# input.net
KiCad netlist of a schematic drawn in Altium Designer
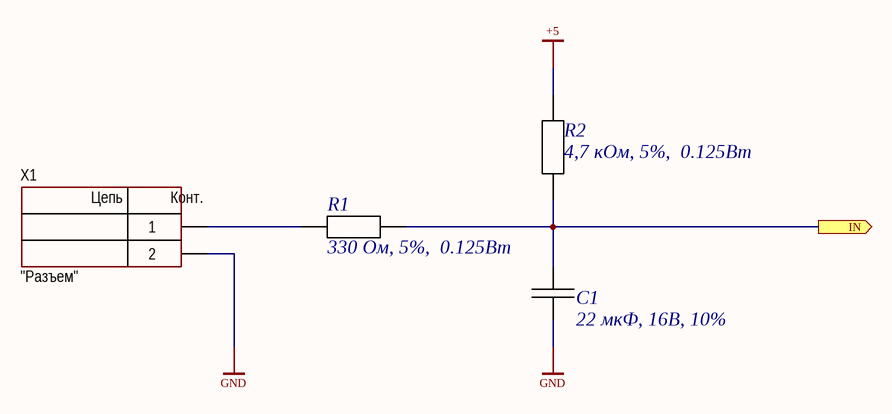
[diagram p0: input.SchDoc]

(export (version "E")
  (design (tool "Eeschema 10.0.6"))
  (components
    (comp (ref "C1")
      (value "22 мкФ, 16В, 10%")
      (footprint "CAP: 1206")
      (description "Конденсатор")
      (fields
        (field (name "PARTNUMBER") "GRM31CR61C226KE15L")
        (field (name "MANUFACTURER") "Murata Manufacturing")
      )
      (libsource (lib "AltiumDatabaseVM") (part "CAP_1"))
    )
    (comp (ref "R1")
      (value "330 Ом, 5%,  0.125Вт")
      (footprint "RES: 0805")
      (description "Бескорпусные толстопленочные резисторы")
      (fields (field (name "POWER") "0,25") (field (name "PARTNUMBER") "RC0805JR-07330RL"))
      (libsource (lib "") (part "Resistor_1"))
    )
    (comp (ref "R2")
      (value "4,7 кОм, 5%,  0.125Вт")
      (footprint "RES: 0805")
      (description "Бескорпусные толстопленочные резисторы")
      (fields (field (name "POWER") "0,25") (field (name "PARTNUMBER") "RC0805JR-074K7L"))
      (libsource (lib "AltiumDatabaseVM") (part "Resistor"))
    )
    (comp (ref "X1")
      (value "~")
      (footprint "TB_2_2.5MM")
      (description "Винтовой клеммный блок c рельефной обоймой, 2 контакта. Серия DG308-2.54")
      (fields
        (field (name "MANUFACTURER") "Китай")
        (field (name "VALUEMANUFACTURERPARTNUMBER") "Terminal connector, 2pin, 3.5mm, 300VAC, 10A")
        (field (name "COMMENTTEXT") "\"Разъем\"")
      )
      (libsource (lib "AltiumDatabaseVM") (part "Connector_terminal_2pin"))
    )
  )
  (nets
    (net (code "1") (name "+5") (class "Default")
      (node (ref "R2") (pin "2") (pinfunction "2_2") (pintype "passive"))
    )
    (net (code "2") (name "/IN") (class "Default")
      (node (ref "C1") (pin "2") (pinfunction "2_2") (pintype "passive"))
      (node (ref "R1") (pin "2") (pinfunction "2_2") (pintype "passive"))
      (node (ref "R2") (pin "1") (pinfunction "1_1") (pintype "passive"))
    )
    (net (code "3") (name "GND") (class "Default")
      (node (ref "C1") (pin "1") (pinfunction "1_1") (pintype "passive"))
      (node (ref "X1") (pin "2") (pinfunction "2_2") (pintype "passive"))
    )
    (net (code "4") (name "Net-(R1-Pad1)") (class "Default")
      (node (ref "R1") (pin "1") (pinfunction "1_1") (pintype "passive"))
      (node (ref "X1") (pin "1") (pinfunction "1_1") (pintype "passive"))
    )
  )
)
